# P13_Configuration.net
KiCad netlist of a schematic drawn in Altium Designer
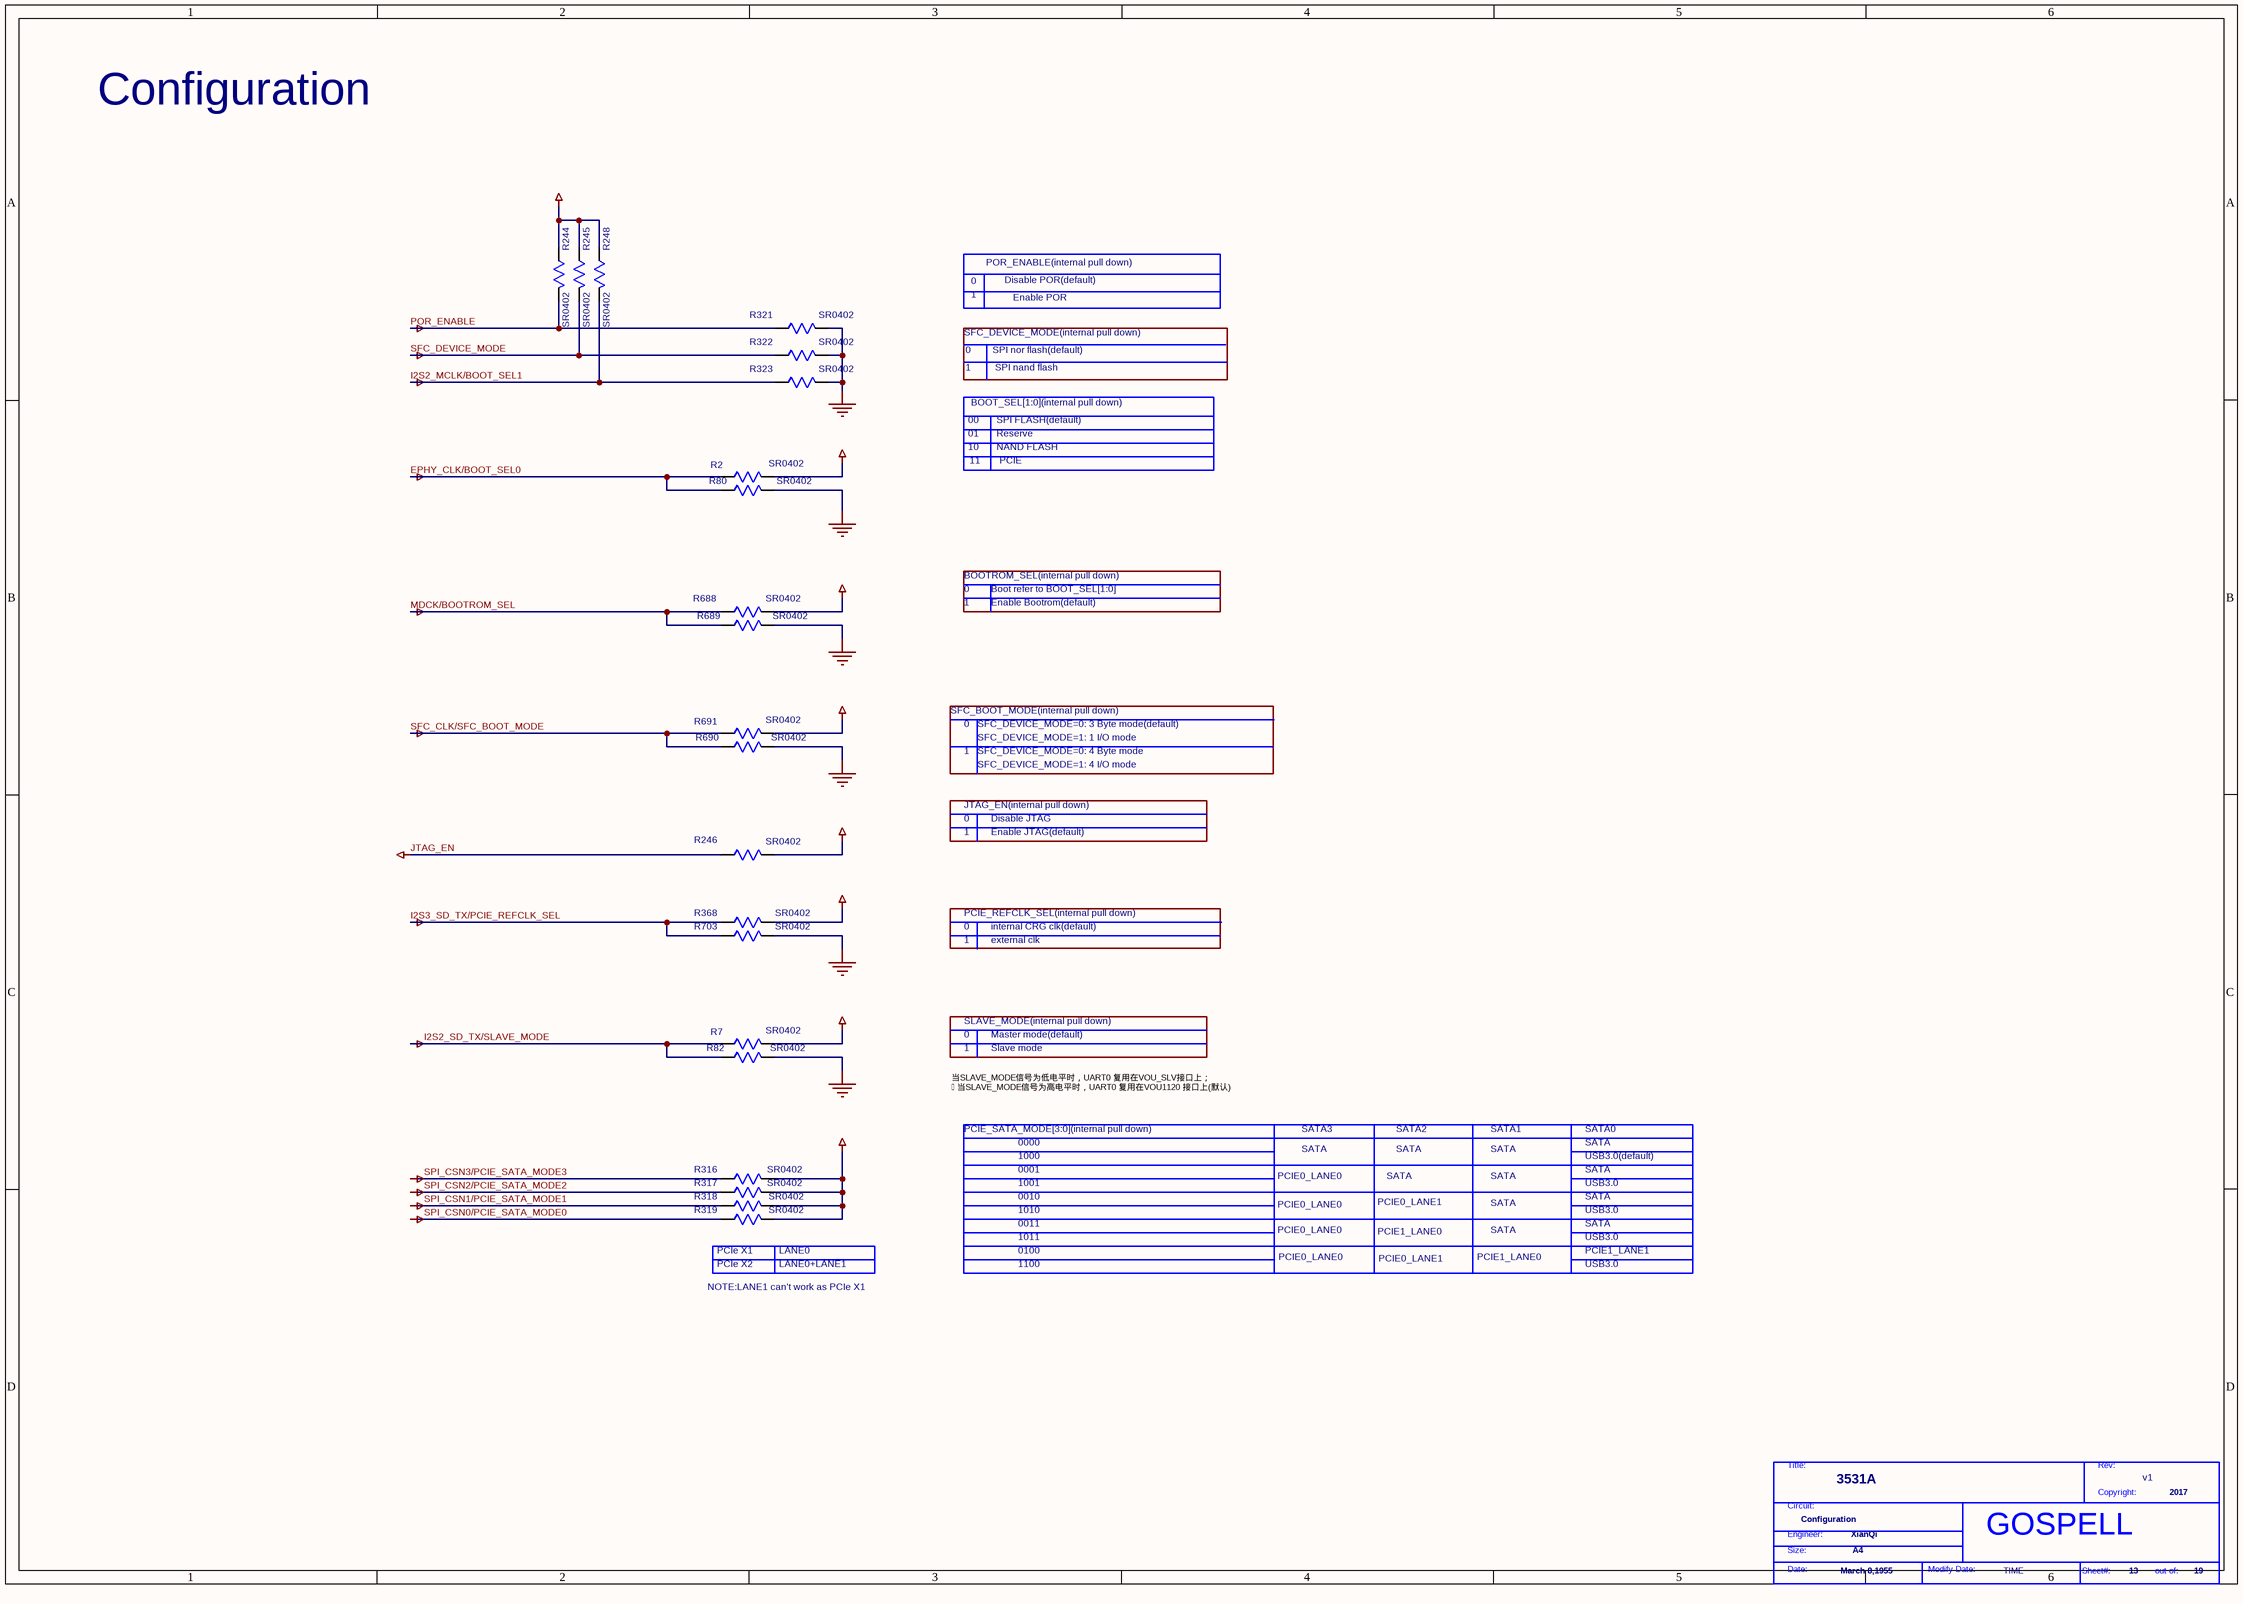
[diagram p0: P13 Configuration.SchDoc]

(export (version "E")
  (design (tool "Eeschema 10.0.6"))
  (components
    (comp (ref "R2") (value "SR0402") (libsource (lib "*") (part "R_1")))
    (comp (ref "R7") (value "SR0402") (libsource (lib "*") (part "R_1")))
    (comp (ref "R80") (value "SR0402") (libsource (lib "*") (part "R_1")))
    (comp (ref "R82") (value "SR0402") (libsource (lib "*") (part "R_1")))
    (comp (ref "R244") (value "SR0402") (libsource (lib "*") (part "R_1")))
    (comp (ref "R245") (value "SR0402") (libsource (lib "*") (part "R_1")))
    (comp (ref "R246") (value "SR0402") (libsource (lib "*") (part "R_1")))
    (comp (ref "R248") (value "SR0402") (libsource (lib "*") (part "R_1")))
    (comp (ref "R316") (value "SR0402") (libsource (lib "*") (part "R_1")))
    (comp (ref "R317") (value "SR0402") (libsource (lib "*") (part "R_1")))
    (comp (ref "R318") (value "SR0402") (libsource (lib "*") (part "R_1")))
    (comp (ref "R319") (value "SR0402") (libsource (lib "*") (part "R_1")))
    (comp (ref "R321") (value "SR0402") (libsource (lib "*") (part "R_1")))
    (comp (ref "R322") (value "SR0402") (libsource (lib "*") (part "R_1")))
    (comp (ref "R323") (value "SR0402") (libsource (lib "*") (part "R_1")))
    (comp (ref "R368") (value "SR0402") (libsource (lib "*") (part "R_1")))
    (comp (ref "R688") (value "SR0402") (libsource (lib "*") (part "R_1")))
    (comp (ref "R689") (value "SR0402") (libsource (lib "*") (part "R_1")))
    (comp (ref "R690") (value "SR0402") (libsource (lib "*") (part "R_1")))
    (comp (ref "R691") (value "SR0402") (libsource (lib "*") (part "R_1")))
    (comp (ref "R703") (value "SR0402") (libsource (lib "*") (part "R_1")))
  )
  (nets
    (net (code "1") (name "3V3") (class "Default")
      (node (ref "R2") (pin "2") (pinfunction "B_2") (pintype "passive"))
      (node (ref "R244") (pin "1") (pinfunction "A_1") (pintype "passive"))
      (node (ref "R245") (pin "1") (pinfunction "A_1") (pintype "passive"))
      (node (ref "R246") (pin "2") (pinfunction "B_2") (pintype "passive"))
      (node (ref "R248") (pin "1") (pinfunction "A_1") (pintype "passive"))
      (node (ref "R316") (pin "2") (pinfunction "B_2") (pintype "passive"))
      (node (ref "R317") (pin "2") (pinfunction "B_2") (pintype "passive"))
      (node (ref "R318") (pin "2") (pinfunction "B_2") (pintype "passive"))
      (node (ref "R319") (pin "2") (pinfunction "B_2") (pintype "passive"))
      (node (ref "R368") (pin "2") (pinfunction "B_2") (pintype "passive"))
      (node (ref "R688") (pin "2") (pinfunction "B_2") (pintype "passive"))
      (node (ref "R691") (pin "2") (pinfunction "B_2") (pintype "passive"))
      (node (ref "R7") (pin "2") (pinfunction "B_2") (pintype "passive"))
    )
    (net (code "2") (name "EPHY_CLK{slash}BOOT_SEL0") (class "Default")
      (node (ref "R2") (pin "1") (pinfunction "A_1") (pintype "passive"))
      (node (ref "R80") (pin "1") (pinfunction "A_1") (pintype "passive"))
    )
    (net (code "3") (name "GND") (class "Default")
      (node (ref "R321") (pin "2") (pinfunction "B_2") (pintype "passive"))
      (node (ref "R322") (pin "2") (pinfunction "B_2") (pintype "passive"))
      (node (ref "R323") (pin "2") (pinfunction "B_2") (pintype "passive"))
      (node (ref "R689") (pin "2") (pinfunction "B_2") (pintype "passive"))
      (node (ref "R690") (pin "2") (pinfunction "B_2") (pintype "passive"))
      (node (ref "R703") (pin "2") (pinfunction "B_2") (pintype "passive"))
      (node (ref "R80") (pin "2") (pinfunction "B_2") (pintype "passive"))
      (node (ref "R82") (pin "2") (pinfunction "B_2") (pintype "passive"))
    )
    (net (code "4") (name "I2S2_MCLK{slash}BOOT_SEL1") (class "Default")
      (node (ref "R248") (pin "2") (pinfunction "B_2") (pintype "passive"))
      (node (ref "R323") (pin "1") (pinfunction "A_1") (pintype "passive"))
    )
    (net (code "5") (name "I2S2_SD_TX{slash}SLAVE_MODE") (class "Default")
      (node (ref "R7") (pin "1") (pinfunction "A_1") (pintype "passive"))
      (node (ref "R82") (pin "1") (pinfunction "A_1") (pintype "passive"))
    )
    (net (code "6") (name "I2S3_SD_TX{slash}PCIE_REFCLK_SEL") (class "Default")
      (node (ref "R368") (pin "1") (pinfunction "A_1") (pintype "passive"))
      (node (ref "R703") (pin "1") (pinfunction "A_1") (pintype "passive"))
    )
    (net (code "7") (name "JTAG_EN") (class "Default")
      (node (ref "R246") (pin "1") (pinfunction "A_1") (pintype "passive"))
    )
    (net (code "8") (name "MDCK{slash}BOOTROM_SEL") (class "Default")
      (node (ref "R688") (pin "1") (pinfunction "A_1") (pintype "passive"))
      (node (ref "R689") (pin "1") (pinfunction "A_1") (pintype "passive"))
    )
    (net (code "9") (name "POR_ENABLE") (class "Default")
      (node (ref "R244") (pin "2") (pinfunction "B_2") (pintype "passive"))
      (node (ref "R321") (pin "1") (pinfunction "A_1") (pintype "passive"))
    )
    (net (code "10") (name "SFC_CLK{slash}SFC_BOOT_MODE") (class "Default")
      (node (ref "R690") (pin "1") (pinfunction "A_1") (pintype "passive"))
      (node (ref "R691") (pin "1") (pinfunction "A_1") (pintype "passive"))
    )
    (net (code "11") (name "SFC_DEVICE_MODE") (class "Default")
      (node (ref "R245") (pin "2") (pinfunction "B_2") (pintype "passive"))
      (node (ref "R322") (pin "1") (pinfunction "A_1") (pintype "passive"))
    )
    (net (code "12") (name "SPI_CSN0{slash}PCIE_SATA_MODE0") (class "Default")
      (node (ref "R319") (pin "1") (pinfunction "A_1") (pintype "passive"))
    )
    (net (code "13") (name "SPI_CSN1{slash}PCIE_SATA_MODE1") (class "Default")
      (node (ref "R318") (pin "1") (pinfunction "A_1") (pintype "passive"))
    )
    (net (code "14") (name "SPI_CSN2{slash}PCIE_SATA_MODE2") (class "Default")
      (node (ref "R317") (pin "1") (pinfunction "A_1") (pintype "passive"))
    )
    (net (code "15") (name "SPI_CSN3{slash}PCIE_SATA_MODE3") (class "Default")
      (node (ref "R316") (pin "1") (pinfunction "A_1") (pintype "passive"))
    )
  )
)
